# RAY_RadioModule.net
KiCad netlist of a schematic drawn in EAGLE
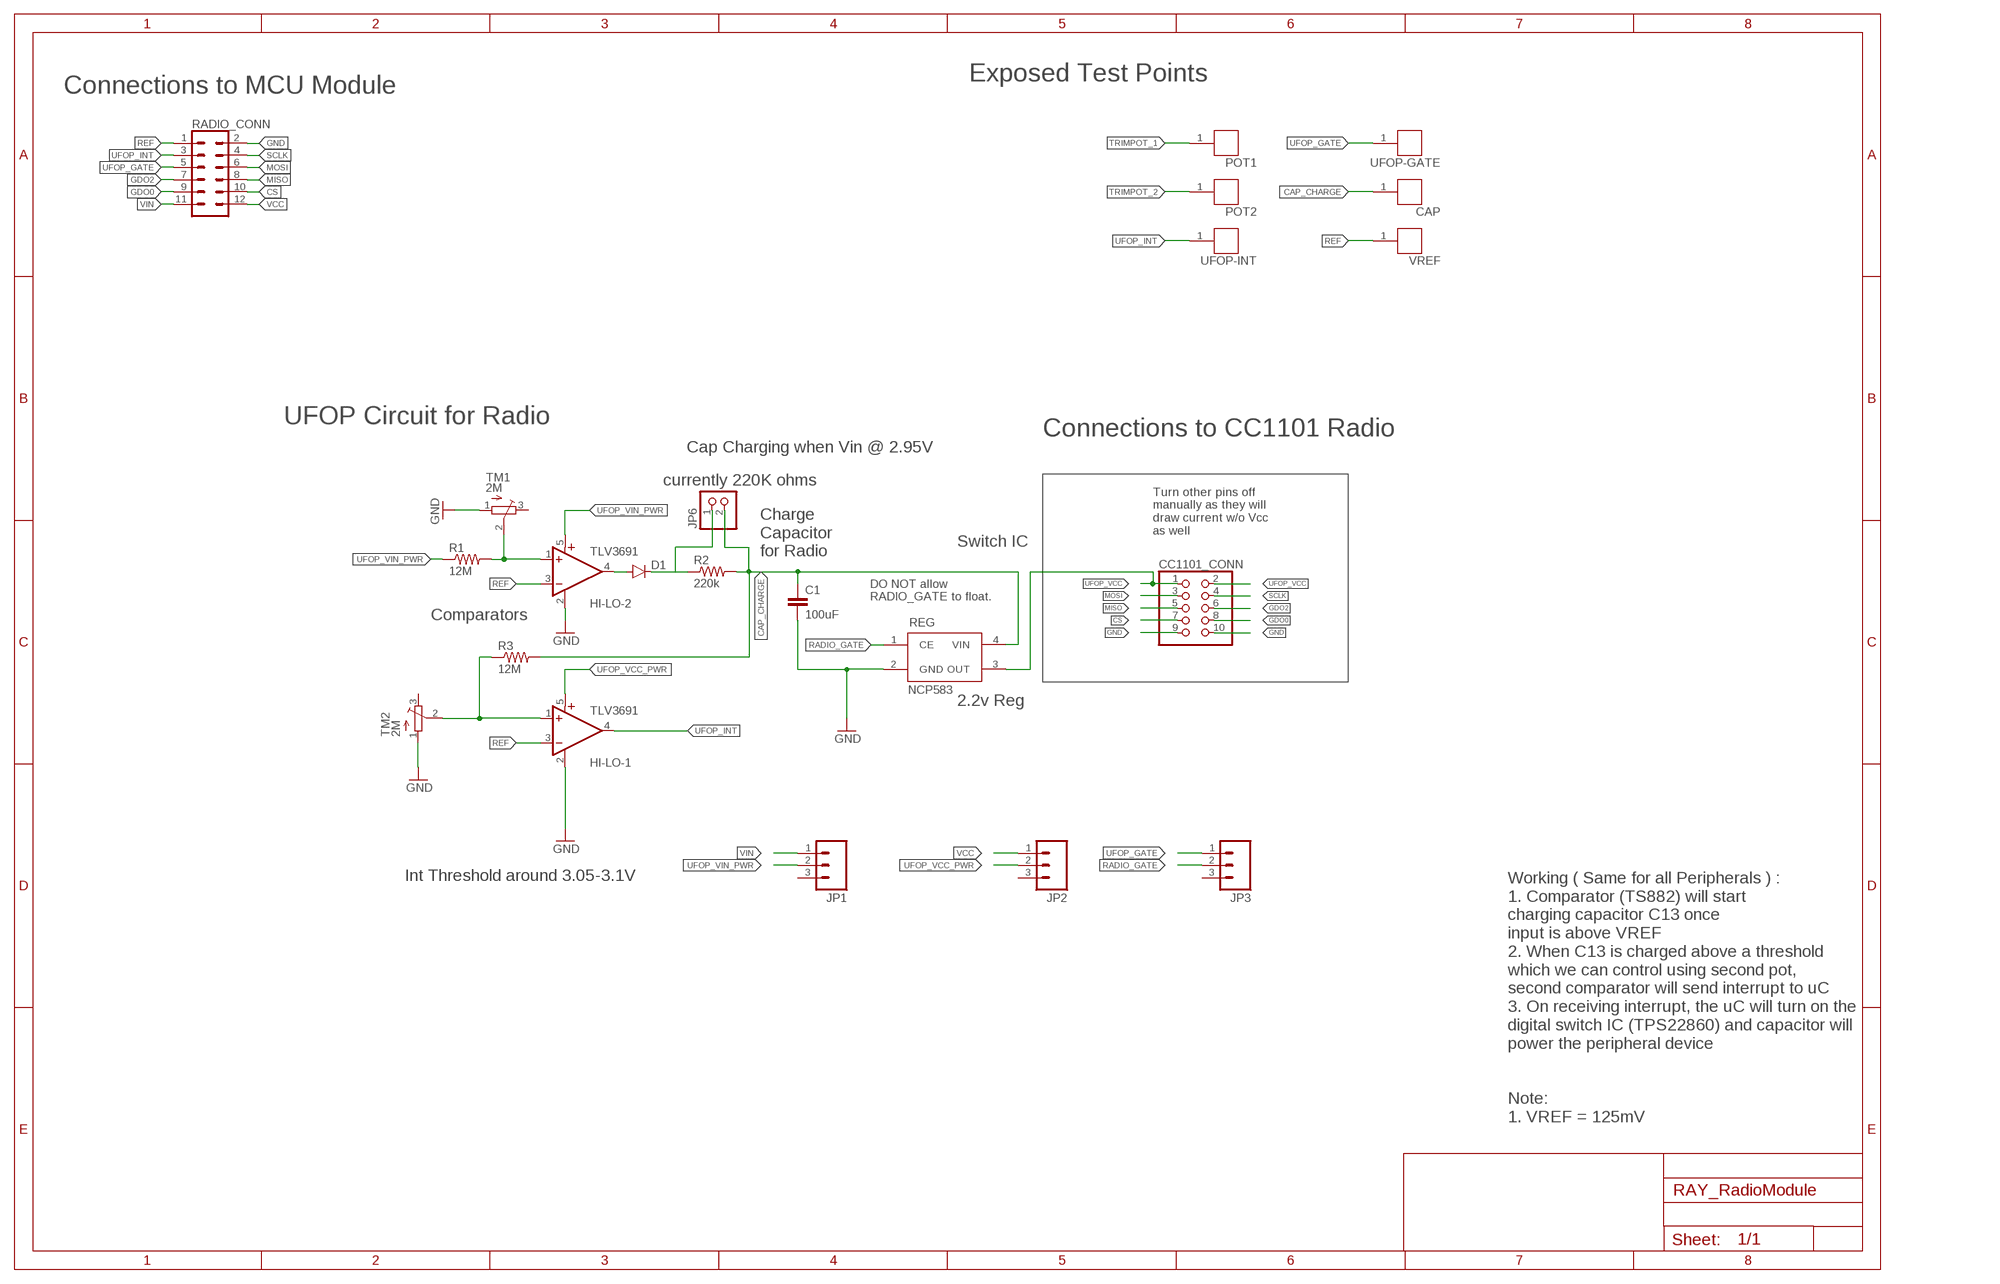
[diagram p0: schematic, sheet 1]

(export (version "E")
  (design (tool "Eeschema 10.0.6"))
  (components
    (comp (ref "C1")
      (value "100uF")
      (footprint "eagle-import:0603-CAP")
      (libsource (lib "eagle-import") (part "CAP0603-CAP"))
    )
    (comp (ref "CAP")
      (value "RCU-0C")
      (footprint "eagle-import:TE_RCU-0C")
      (fields
        (field (name "COMMENT") "RCU-0C _1625854-3_")
        (field (name "MF") "TE Connectivity")
        (field (name "TOLERANCE") "0%")
      )
      (libsource (lib "eagle-import") (part "RCU-0C"))
    )
    (comp (ref "CC1101_CONN")
      (value "PINHD-2X5")
      (footprint "eagle-import:2X05")
      (libsource (lib "eagle-import") (part "PINHD-2X5"))
    )
    (comp (ref "D1")
      (value "DIODESOD523")
      (footprint "eagle-import:SOD523")
      (libsource (lib "eagle-import") (part "DIODESOD523"))
    )
    (comp (ref "HI-LO-1")
      (value "TLV3691")
      (footprint "eagle-import:SC70-5")
      (libsource (lib "eagle-import") (part "TLV3691"))
    )
    (comp (ref "HI-LO-2")
      (value "TLV3691")
      (footprint "eagle-import:SC70-5")
      (libsource (lib "eagle-import") (part "TLV3691"))
    )
    (comp (ref "JP1")
      (value "M03")
      (footprint "eagle-import:1X03-1.27MM")
      (libsource (lib "eagle-import") (part "M03"))
    )
    (comp (ref "JP2")
      (value "M03")
      (footprint "eagle-import:1X03-1.27MM")
      (libsource (lib "eagle-import") (part "M03"))
    )
    (comp (ref "JP3")
      (value "M03")
      (footprint "eagle-import:1X03-1.27MM")
      (libsource (lib "eagle-import") (part "M03"))
    )
    (comp (ref "JP6")
      (value "PINHD-1X2")
      (footprint "eagle-import:1X02")
      (libsource (lib "eagle-import") (part "PINHD-1X2"))
    )
    (comp (ref "POT1")
      (value "RCU-0C")
      (footprint "eagle-import:TE_RCU-0C")
      (fields
        (field (name "COMMENT") "RCU-0C _1625854-3_")
        (field (name "MF") "TE Connectivity")
        (field (name "TOLERANCE") "0%")
      )
      (libsource (lib "eagle-import") (part "RCU-0C"))
    )
    (comp (ref "POT2")
      (value "RCU-0C")
      (footprint "eagle-import:TE_RCU-0C")
      (fields
        (field (name "COMMENT") "RCU-0C _1625854-3_")
        (field (name "MF") "TE Connectivity")
        (field (name "TOLERANCE") "0%")
      )
      (libsource (lib "eagle-import") (part "RCU-0C"))
    )
    (comp (ref "R1")
      (value "12M")
      (footprint "eagle-import:0603-RES")
      (libsource (lib "eagle-import") (part "RESISTOR0603"))
    )
    (comp (ref "R2")
      (value "220k")
      (footprint "eagle-import:0603-RES")
      (libsource (lib "eagle-import") (part "RESISTOR0603"))
    )
    (comp (ref "R3")
      (value "12M")
      (footprint "eagle-import:0603-RES")
      (libsource (lib "eagle-import") (part "RESISTOR0603"))
    )
    (comp (ref "RADIO_CONN")
      (value "CONN_06X2PTH_FEMALE")
      (footprint "eagle-import:2X6")
      (libsource (lib "eagle-import") (part "CONN_06X2PTH_FEMALE"))
    )
    (comp (ref "REG")
      (value "NCP583")
      (footprint "eagle-import:SC82-AB_1PRIMARY")
      (libsource (lib "eagle-import") (part "NCP583"))
    )
    (comp (ref "TM1")
      (value "2M")
      (footprint "eagle-import:TC33X")
      (libsource (lib "eagle-import") (part "TRIMPOTTC33X"))
    )
    (comp (ref "TM2")
      (value "2M")
      (footprint "eagle-import:TC33X")
      (libsource (lib "eagle-import") (part "TRIMPOTTC33X"))
    )
    (comp (ref "UFOP-GATE")
      (value "RCU-0C")
      (footprint "eagle-import:TE_RCU-0C")
      (fields
        (field (name "COMMENT") "RCU-0C _1625854-3_")
        (field (name "MF") "TE Connectivity")
        (field (name "TOLERANCE") "0%")
      )
      (libsource (lib "eagle-import") (part "RCU-0C"))
    )
    (comp (ref "UFOP-INT")
      (value "RCU-0C")
      (footprint "eagle-import:TE_RCU-0C")
      (fields
        (field (name "COMMENT") "RCU-0C _1625854-3_")
        (field (name "MF") "TE Connectivity")
        (field (name "TOLERANCE") "0%")
      )
      (libsource (lib "eagle-import") (part "RCU-0C"))
    )
    (comp (ref "VREF")
      (value "RCU-0C")
      (footprint "eagle-import:TE_RCU-0C")
      (fields
        (field (name "COMMENT") "RCU-0C _1625854-3_")
        (field (name "MF") "TE Connectivity")
        (field (name "TOLERANCE") "0%")
      )
      (libsource (lib "eagle-import") (part "RCU-0C"))
    )
  )
  (nets
    (net (code "1") (name "CAP_CHARGE") (class "Default")
      (node (ref "C1") (pin "1") (pinfunction "1_1") (pintype "passive"))
      (node (ref "CAP") (pin "1") (pinfunction "1_1") (pintype "passive"))
      (node (ref "JP6") (pin "2") (pinfunction "2_2") (pintype "passive"))
      (node (ref "R2") (pin "2") (pinfunction "2_2") (pintype "passive"))
      (node (ref "R3") (pin "2") (pinfunction "2_2") (pintype "passive"))
      (node (ref "REG") (pin "4") (pinfunction "VIN_4") (pintype "bidirectional"))
    )
    (net (code "2") (name "CS") (class "Default")
      (node (ref "CC1101_CONN") (pin "7") (pinfunction "7_7") (pintype "passive"))
      (node (ref "RADIO_CONN") (pin "10") (pinfunction "10_10") (pintype "passive"))
    )
    (net (code "3") (name "GDO0") (class "Default")
      (node (ref "CC1101_CONN") (pin "8") (pinfunction "8_8") (pintype "passive"))
      (node (ref "RADIO_CONN") (pin "9") (pinfunction "9_9") (pintype "passive"))
    )
    (net (code "4") (name "GDO2") (class "Default")
      (node (ref "CC1101_CONN") (pin "6") (pinfunction "6_6") (pintype "passive"))
      (node (ref "RADIO_CONN") (pin "7") (pinfunction "7_7") (pintype "passive"))
    )
    (net (code "5") (name "GND") (class "Default")
      (node (ref "C1") (pin "2") (pinfunction "2_2") (pintype "passive"))
      (node (ref "CC1101_CONN") (pin "10") (pinfunction "10_10") (pintype "passive"))
      (node (ref "CC1101_CONN") (pin "9") (pinfunction "9_9") (pintype "passive"))
      (node (ref "HI-LO-1") (pin "2") (pinfunction "GND_2") (pintype "power_in"))
      (node (ref "HI-LO-2") (pin "2") (pinfunction "GND_2") (pintype "power_in"))
      (node (ref "RADIO_CONN") (pin "2") (pinfunction "2_2") (pintype "passive"))
      (node (ref "REG") (pin "2") (pinfunction "GND_2") (pintype "bidirectional"))
      (node (ref "TM1") (pin "1") (pinfunction "A_1") (pintype "passive"))
      (node (ref "TM2") (pin "1") (pinfunction "A_1") (pintype "passive"))
    )
    (net (code "6") (name "MISO") (class "Default")
      (node (ref "CC1101_CONN") (pin "5") (pinfunction "5_5") (pintype "passive"))
      (node (ref "RADIO_CONN") (pin "8") (pinfunction "8_8") (pintype "passive"))
    )
    (net (code "7") (name "MOSI") (class "Default")
      (node (ref "CC1101_CONN") (pin "3") (pinfunction "3_3") (pintype "passive"))
      (node (ref "RADIO_CONN") (pin "6") (pinfunction "6_6") (pintype "passive"))
    )
    (net (code "8") (name "Net-(D1-PadC)") (class "Default")
      (node (ref "D1") (pin "C") (pinfunction "C_C") (pintype "passive"))
      (node (ref "JP6") (pin "1") (pinfunction "1_1") (pintype "passive"))
      (node (ref "R2") (pin "1") (pinfunction "1_1") (pintype "passive"))
    )
    (net (code "9") (name "Net-(HI-LO-2-OUT)") (class "Default")
      (node (ref "D1") (pin "A") (pinfunction "A_A") (pintype "passive"))
      (node (ref "HI-LO-2") (pin "4") (pinfunction "OUT_4") (pintype "output"))
    )
    (net (code "10") (name "RADIO_GATE") (class "Default")
      (node (ref "JP3") (pin "2") (pinfunction "2_2") (pintype "passive"))
      (node (ref "REG") (pin "1") (pinfunction "CE_1") (pintype "bidirectional"))
    )
    (net (code "11") (name "REF") (class "Default")
      (node (ref "HI-LO-1") (pin "3") (pinfunction "-IN_3") (pintype "input"))
      (node (ref "HI-LO-2") (pin "3") (pinfunction "-IN_3") (pintype "input"))
      (node (ref "RADIO_CONN") (pin "1") (pinfunction "1_1") (pintype "passive"))
      (node (ref "VREF") (pin "1") (pinfunction "1_1") (pintype "passive"))
    )
    (net (code "12") (name "SCLK") (class "Default")
      (node (ref "CC1101_CONN") (pin "4") (pinfunction "4_4") (pintype "passive"))
      (node (ref "RADIO_CONN") (pin "4") (pinfunction "4_4") (pintype "passive"))
    )
    (net (code "13") (name "TRIMPOT_1") (class "Default")
      (node (ref "HI-LO-2") (pin "1") (pinfunction "+IN_1") (pintype "input"))
      (node (ref "POT1") (pin "1") (pinfunction "1_1") (pintype "passive"))
      (node (ref "R1") (pin "2") (pinfunction "2_2") (pintype "passive"))
      (node (ref "TM1") (pin "2") (pinfunction "S_2") (pintype "passive"))
    )
    (net (code "14") (name "TRIMPOT_2") (class "Default")
      (node (ref "HI-LO-1") (pin "1") (pinfunction "+IN_1") (pintype "input"))
      (node (ref "POT2") (pin "1") (pinfunction "1_1") (pintype "passive"))
      (node (ref "R3") (pin "1") (pinfunction "1_1") (pintype "passive"))
      (node (ref "TM2") (pin "2") (pinfunction "S_2") (pintype "passive"))
    )
    (net (code "15") (name "UFOP_GATE") (class "Default")
      (node (ref "JP3") (pin "1") (pinfunction "1_1") (pintype "passive"))
      (node (ref "RADIO_CONN") (pin "5") (pinfunction "5_5") (pintype "passive"))
      (node (ref "UFOP-GATE") (pin "1") (pinfunction "1_1") (pintype "passive"))
    )
    (net (code "16") (name "UFOP_INT") (class "Default")
      (node (ref "HI-LO-1") (pin "4") (pinfunction "OUT_4") (pintype "output"))
      (node (ref "RADIO_CONN") (pin "3") (pinfunction "3_3") (pintype "passive"))
      (node (ref "UFOP-INT") (pin "1") (pinfunction "1_1") (pintype "passive"))
    )
    (net (code "17") (name "UFOP_VCC") (class "Default")
      (node (ref "CC1101_CONN") (pin "1") (pinfunction "1_1") (pintype "passive"))
      (node (ref "CC1101_CONN") (pin "2") (pinfunction "2_2") (pintype "passive"))
      (node (ref "REG") (pin "3") (pinfunction "OUT_3") (pintype "bidirectional"))
    )
    (net (code "18") (name "UFOP_VCC_PWR") (class "Default")
      (node (ref "HI-LO-1") (pin "5") (pinfunction "V+_5") (pintype "power_in"))
      (node (ref "JP2") (pin "2") (pinfunction "2_2") (pintype "passive"))
    )
    (net (code "19") (name "UFOP_VIN_PWR") (class "Default")
      (node (ref "HI-LO-2") (pin "5") (pinfunction "V+_5") (pintype "power_in"))
      (node (ref "JP1") (pin "2") (pinfunction "2_2") (pintype "passive"))
      (node (ref "R1") (pin "1") (pinfunction "1_1") (pintype "passive"))
    )
    (net (code "20") (name "VCC") (class "Default")
      (node (ref "JP2") (pin "1") (pinfunction "1_1") (pintype "passive"))
      (node (ref "RADIO_CONN") (pin "12") (pinfunction "12_12") (pintype "passive"))
    )
    (net (code "21") (name "VIN") (class "Default")
      (node (ref "JP1") (pin "1") (pinfunction "1_1") (pintype "passive"))
      (node (ref "RADIO_CONN") (pin "11") (pinfunction "11_11") (pintype "passive"))
    )
    (net (code "22") (name "unconnected-(JP1-Pad3)") (class "Default")
      (node (ref "JP1") (pin "3") (pinfunction "3_3") (pintype "passive"))
    )
    (net (code "23") (name "unconnected-(JP2-Pad3)") (class "Default")
      (node (ref "JP2") (pin "3") (pinfunction "3_3") (pintype "passive"))
    )
    (net (code "24") (name "unconnected-(JP3-Pad3)") (class "Default")
      (node (ref "JP3") (pin "3") (pinfunction "3_3") (pintype "passive"))
    )
    (net (code "25") (name "unconnected-(TM1-E-Pad3)") (class "Default")
      (node (ref "TM1") (pin "3") (pinfunction "E_3") (pintype "passive"))
    )
    (net (code "26") (name "unconnected-(TM2-E-Pad3)") (class "Default")
      (node (ref "TM2") (pin "3") (pinfunction "E_3") (pintype "passive"))
    )
  )
)
